# BigDigit.net
KiCad netlist of a schematic drawn in EAGLE
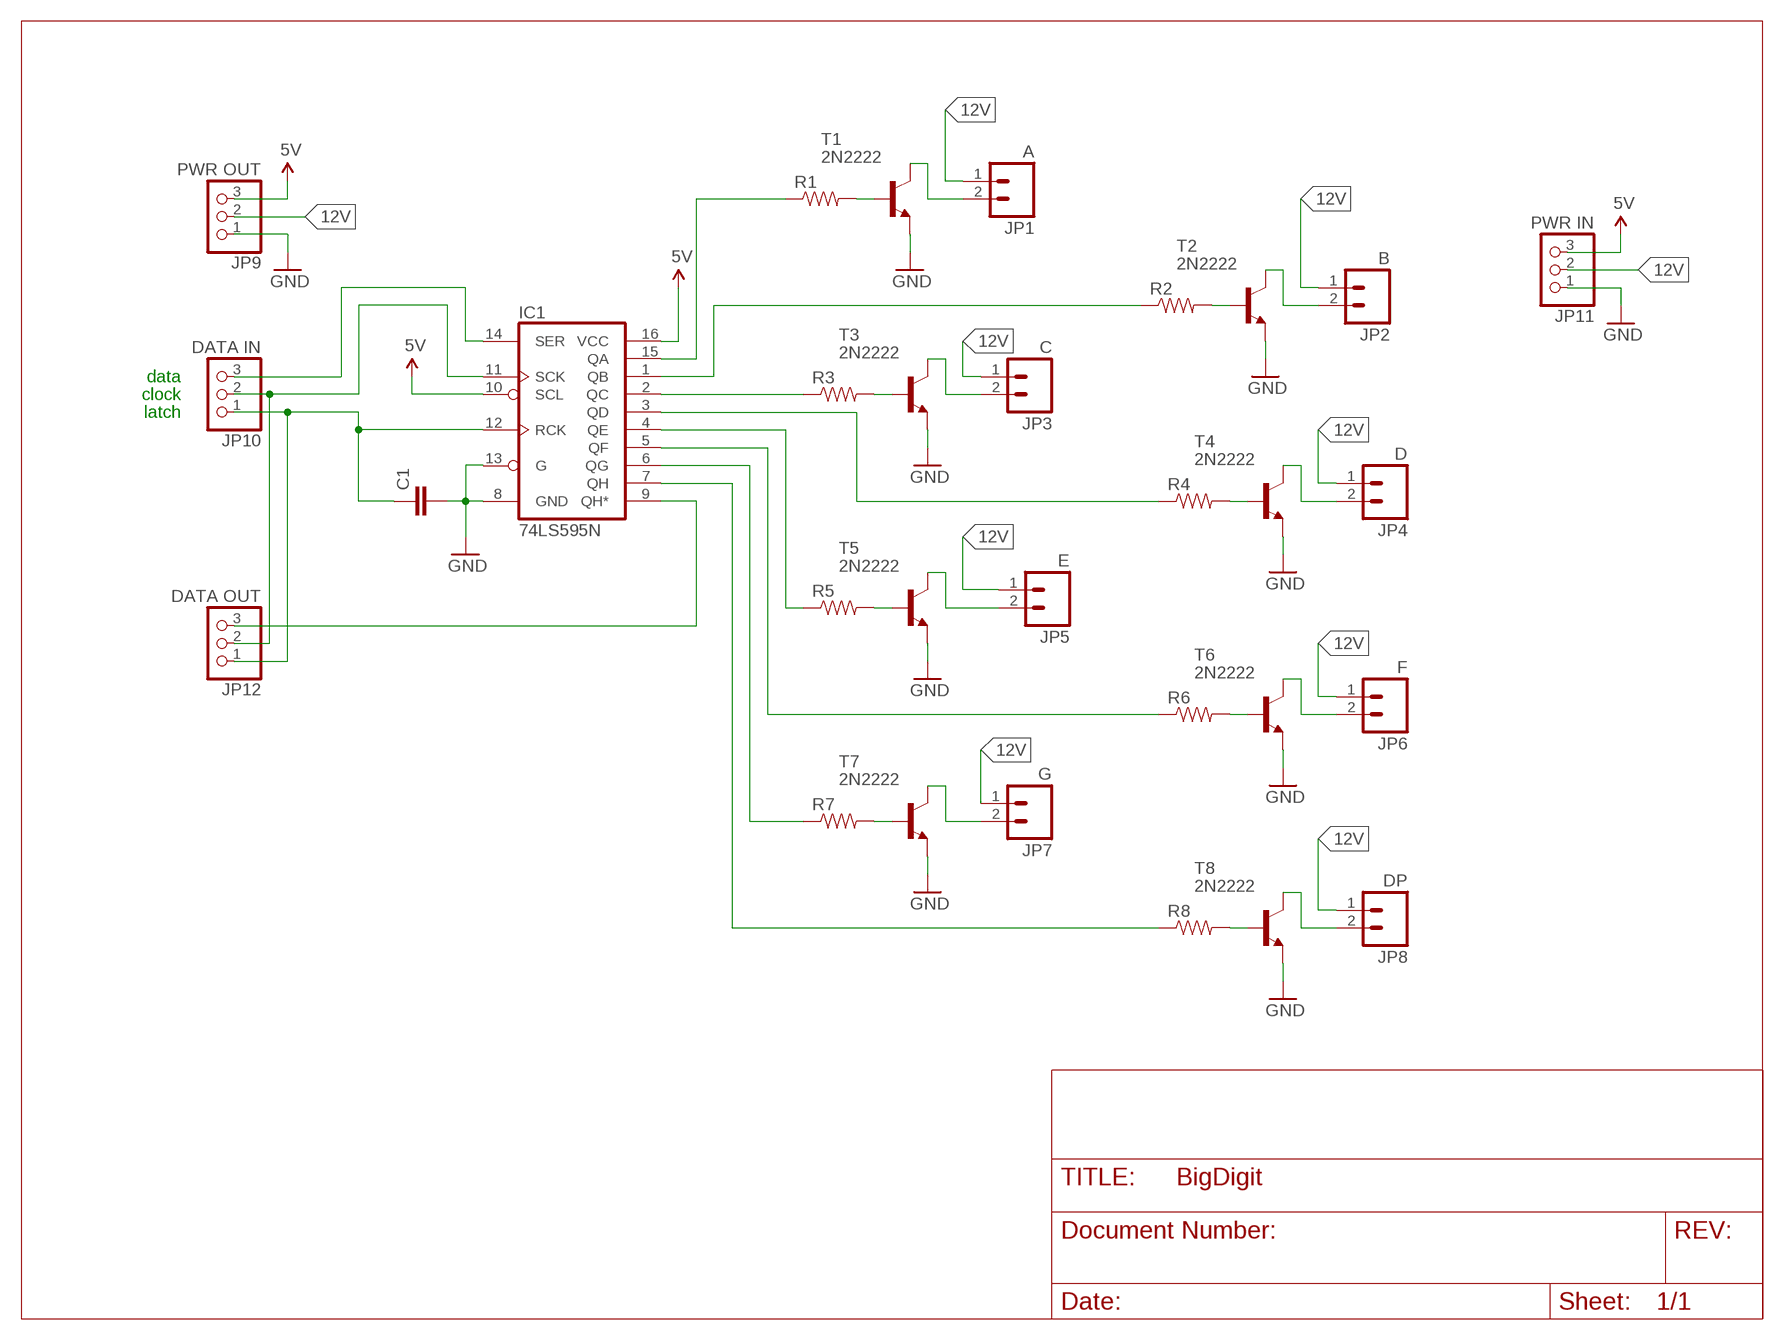
[diagram p0: schematic, sheet 1]

(export (version "E")
  (design (tool "Eeschema 10.0.6"))
  (components
    (comp (ref "C1")
      (value "0.1UF-50V-20%(PTH)KIT-EZ")
      (footprint "eagle-import:CAP-PTH-SMALL-KIT")
      (libsource (lib "eagle-import") (part "0.1UF-50V-20%(PTH)KIT-EZ"))
    )
    (comp (ref "IC1")
      (value "74LS595N")
      (footprint "eagle-import:DIL16")
      (libsource (lib "eagle-import") (part "74595NLS"))
    )
    (comp (ref "JP1")
      (value "A")
      (footprint "eagle-import:1X02")
      (libsource (lib "eagle-import") (part "M02PTH"))
    )
    (comp (ref "JP2")
      (value "B")
      (footprint "eagle-import:1X02")
      (libsource (lib "eagle-import") (part "M02PTH"))
    )
    (comp (ref "JP3")
      (value "C")
      (footprint "eagle-import:1X02")
      (libsource (lib "eagle-import") (part "M02PTH"))
    )
    (comp (ref "JP4")
      (value "D")
      (footprint "eagle-import:1X02")
      (libsource (lib "eagle-import") (part "M02PTH"))
    )
    (comp (ref "JP5")
      (value "E")
      (footprint "eagle-import:1X02")
      (libsource (lib "eagle-import") (part "M02PTH"))
    )
    (comp (ref "JP6")
      (value "F")
      (footprint "eagle-import:1X02")
      (libsource (lib "eagle-import") (part "M02PTH"))
    )
    (comp (ref "JP7")
      (value "G")
      (footprint "eagle-import:1X02")
      (libsource (lib "eagle-import") (part "M02PTH"))
    )
    (comp (ref "JP8")
      (value "DP")
      (footprint "eagle-import:1X02")
      (libsource (lib "eagle-import") (part "M02PTH"))
    )
    (comp (ref "JP9")
      (value "PWR OUT")
      (footprint "eagle-import:1X03-CLEANBIG")
      (libsource (lib "eagle-import") (part "PINHD-1X3CB"))
    )
    (comp (ref "JP10")
      (value "DATA IN")
      (footprint "eagle-import:1X03-CLEANBIG")
      (libsource (lib "eagle-import") (part "PINHD-1X3CB"))
    )
    (comp (ref "JP11")
      (value "PWR IN")
      (footprint "eagle-import:1X03-CLEANBIG")
      (libsource (lib "eagle-import") (part "PINHD-1X3CB"))
    )
    (comp (ref "JP12")
      (value "DATA OUT")
      (footprint "eagle-import:1X03-CLEANBIG")
      (libsource (lib "eagle-import") (part "PINHD-1X3CB"))
    )
    (comp (ref "R1")
      (value "RESISTORPTH-1/4W-VERT")
      (footprint "eagle-import:AXIAL-0.1")
      (libsource (lib "eagle-import") (part "RESISTORPTH-1/4W-VERT"))
    )
    (comp (ref "R2")
      (value "RESISTORPTH-1/4W-VERT")
      (footprint "eagle-import:AXIAL-0.1")
      (libsource (lib "eagle-import") (part "RESISTORPTH-1/4W-VERT"))
    )
    (comp (ref "R3")
      (value "RESISTORPTH-1/4W-VERT")
      (footprint "eagle-import:AXIAL-0.1")
      (libsource (lib "eagle-import") (part "RESISTORPTH-1/4W-VERT"))
    )
    (comp (ref "R4")
      (value "RESISTORPTH-1/4W-VERT")
      (footprint "eagle-import:AXIAL-0.1")
      (libsource (lib "eagle-import") (part "RESISTORPTH-1/4W-VERT"))
    )
    (comp (ref "R5")
      (value "RESISTORPTH-1/4W-VERT")
      (footprint "eagle-import:AXIAL-0.1")
      (libsource (lib "eagle-import") (part "RESISTORPTH-1/4W-VERT"))
    )
    (comp (ref "R6")
      (value "RESISTORPTH-1/4W-VERT")
      (footprint "eagle-import:AXIAL-0.1")
      (libsource (lib "eagle-import") (part "RESISTORPTH-1/4W-VERT"))
    )
    (comp (ref "R7")
      (value "RESISTORPTH-1/4W-VERT")
      (footprint "eagle-import:AXIAL-0.1")
      (libsource (lib "eagle-import") (part "RESISTORPTH-1/4W-VERT"))
    )
    (comp (ref "R8")
      (value "RESISTORPTH-1/4W-VERT")
      (footprint "eagle-import:AXIAL-0.1")
      (libsource (lib "eagle-import") (part "RESISTORPTH-1/4W-VERT"))
    )
    (comp (ref "T1")
      (value "2N2222")
      (footprint "eagle-import:TO92-EBC-OVAL")
      (libsource (lib "eagle-import") (part "2N2222"))
    )
    (comp (ref "T2")
      (value "2N2222")
      (footprint "eagle-import:TO92-EBC-OVAL")
      (libsource (lib "eagle-import") (part "2N2222"))
    )
    (comp (ref "T3")
      (value "2N2222")
      (footprint "eagle-import:TO92-EBC-OVAL")
      (libsource (lib "eagle-import") (part "2N2222"))
    )
    (comp (ref "T4")
      (value "2N2222")
      (footprint "eagle-import:TO92-EBC-OVAL")
      (libsource (lib "eagle-import") (part "2N2222"))
    )
    (comp (ref "T5")
      (value "2N2222")
      (footprint "eagle-import:TO92-EBC-OVAL")
      (libsource (lib "eagle-import") (part "2N2222"))
    )
    (comp (ref "T6")
      (value "2N2222")
      (footprint "eagle-import:TO92-EBC-OVAL")
      (libsource (lib "eagle-import") (part "2N2222"))
    )
    (comp (ref "T7")
      (value "2N2222")
      (footprint "eagle-import:TO92-EBC-OVAL")
      (libsource (lib "eagle-import") (part "2N2222"))
    )
    (comp (ref "T8")
      (value "2N2222")
      (footprint "eagle-import:TO92-EBC-OVAL")
      (libsource (lib "eagle-import") (part "2N2222"))
    )
  )
  (nets
    (net (code "1") (name "5V") (class "Default")
      (node (ref "IC1") (pin "10") (pinfunction "SCL_10") (pintype "input"))
      (node (ref "IC1") (pin "16") (pinfunction "VCC_16") (pintype "power_in"))
      (node (ref "JP11") (pin "3") (pinfunction "3_3") (pintype "passive"))
      (node (ref "JP9") (pin "3") (pinfunction "3_3") (pintype "passive"))
    )
    (net (code "2") (name "12V") (class "Default")
      (node (ref "JP1") (pin "1") (pinfunction "1_1") (pintype "passive"))
      (node (ref "JP11") (pin "2") (pinfunction "2_2") (pintype "passive"))
      (node (ref "JP2") (pin "1") (pinfunction "1_1") (pintype "passive"))
      (node (ref "JP3") (pin "1") (pinfunction "1_1") (pintype "passive"))
      (node (ref "JP4") (pin "1") (pinfunction "1_1") (pintype "passive"))
      (node (ref "JP5") (pin "1") (pinfunction "1_1") (pintype "passive"))
      (node (ref "JP6") (pin "1") (pinfunction "1_1") (pintype "passive"))
      (node (ref "JP7") (pin "1") (pinfunction "1_1") (pintype "passive"))
      (node (ref "JP8") (pin "1") (pinfunction "1_1") (pintype "passive"))
      (node (ref "JP9") (pin "2") (pinfunction "2_2") (pintype "passive"))
    )
    (net (code "3") (name "GND") (class "Default")
      (node (ref "C1") (pin "2") (pinfunction "2_2") (pintype "passive"))
      (node (ref "IC1") (pin "13") (pinfunction "G_13") (pintype "input"))
      (node (ref "IC1") (pin "8") (pinfunction "GND_8") (pintype "power_in"))
      (node (ref "JP11") (pin "1") (pinfunction "1_1") (pintype "passive"))
      (node (ref "JP9") (pin "1") (pinfunction "1_1") (pintype "passive"))
      (node (ref "T1") (pin "E") (pinfunction "E_E") (pintype "passive"))
      (node (ref "T2") (pin "E") (pinfunction "E_E") (pintype "passive"))
      (node (ref "T3") (pin "E") (pinfunction "E_E") (pintype "passive"))
      (node (ref "T4") (pin "E") (pinfunction "E_E") (pintype "passive"))
      (node (ref "T5") (pin "E") (pinfunction "E_E") (pintype "passive"))
      (node (ref "T6") (pin "E") (pinfunction "E_E") (pintype "passive"))
      (node (ref "T7") (pin "E") (pinfunction "E_E") (pintype "passive"))
      (node (ref "T8") (pin "E") (pinfunction "E_E") (pintype "passive"))
    )
    (net (code "4") (name "Net-(IC1-QA)") (class "Default")
      (node (ref "IC1") (pin "15") (pinfunction "QA_15") (pintype "tri_state"))
      (node (ref "R1") (pin "P$1") (pinfunction "1_P$1") (pintype "passive"))
    )
    (net (code "5") (name "Net-(IC1-QB)") (class "Default")
      (node (ref "IC1") (pin "1") (pinfunction "QB_1") (pintype "tri_state"))
      (node (ref "R2") (pin "P$1") (pinfunction "1_P$1") (pintype "passive"))
    )
    (net (code "6") (name "Net-(IC1-QC)") (class "Default")
      (node (ref "IC1") (pin "2") (pinfunction "QC_2") (pintype "tri_state"))
      (node (ref "R3") (pin "P$1") (pinfunction "1_P$1") (pintype "passive"))
    )
    (net (code "7") (name "Net-(IC1-QD)") (class "Default")
      (node (ref "IC1") (pin "3") (pinfunction "QD_3") (pintype "tri_state"))
      (node (ref "R4") (pin "P$1") (pinfunction "1_P$1") (pintype "passive"))
    )
    (net (code "8") (name "Net-(IC1-QE)") (class "Default")
      (node (ref "IC1") (pin "4") (pinfunction "QE_4") (pintype "tri_state"))
      (node (ref "R5") (pin "P$1") (pinfunction "1_P$1") (pintype "passive"))
    )
    (net (code "9") (name "Net-(IC1-QF)") (class "Default")
      (node (ref "IC1") (pin "5") (pinfunction "QF_5") (pintype "tri_state"))
      (node (ref "R6") (pin "P$1") (pinfunction "1_P$1") (pintype "passive"))
    )
    (net (code "10") (name "Net-(IC1-QG)") (class "Default")
      (node (ref "IC1") (pin "6") (pinfunction "QG_6") (pintype "tri_state"))
      (node (ref "R7") (pin "P$1") (pinfunction "1_P$1") (pintype "passive"))
    )
    (net (code "11") (name "Net-(IC1-QH)") (class "Default")
      (node (ref "IC1") (pin "7") (pinfunction "QH_7") (pintype "tri_state"))
      (node (ref "R8") (pin "P$1") (pinfunction "1_P$1") (pintype "passive"))
    )
    (net (code "12") (name "Net-(IC1-QH*)") (class "Default")
      (node (ref "IC1") (pin "9") (pinfunction "QH*_9") (pintype "tri_state"))
      (node (ref "JP12") (pin "3") (pinfunction "3_3") (pintype "passive"))
    )
    (net (code "13") (name "Net-(IC1-RCK)") (class "Default")
      (node (ref "C1") (pin "1") (pinfunction "1_1") (pintype "passive"))
      (node (ref "IC1") (pin "12") (pinfunction "RCK_12") (pintype "input"))
      (node (ref "JP10") (pin "1") (pinfunction "1_1") (pintype "passive"))
      (node (ref "JP12") (pin "1") (pinfunction "1_1") (pintype "passive"))
    )
    (net (code "14") (name "Net-(IC1-SCK)") (class "Default")
      (node (ref "IC1") (pin "11") (pinfunction "SCK_11") (pintype "input"))
      (node (ref "JP10") (pin "2") (pinfunction "2_2") (pintype "passive"))
      (node (ref "JP12") (pin "2") (pinfunction "2_2") (pintype "passive"))
    )
    (net (code "15") (name "Net-(IC1-SER)") (class "Default")
      (node (ref "IC1") (pin "14") (pinfunction "SER_14") (pintype "input"))
      (node (ref "JP10") (pin "3") (pinfunction "3_3") (pintype "passive"))
    )
    (net (code "16") (name "Net-(JP1-Pad2)") (class "Default")
      (node (ref "JP1") (pin "2") (pinfunction "2_2") (pintype "passive"))
      (node (ref "T1") (pin "C") (pinfunction "C_C") (pintype "passive"))
    )
    (net (code "17") (name "Net-(JP2-Pad2)") (class "Default")
      (node (ref "JP2") (pin "2") (pinfunction "2_2") (pintype "passive"))
      (node (ref "T2") (pin "C") (pinfunction "C_C") (pintype "passive"))
    )
    (net (code "18") (name "Net-(JP3-Pad2)") (class "Default")
      (node (ref "JP3") (pin "2") (pinfunction "2_2") (pintype "passive"))
      (node (ref "T3") (pin "C") (pinfunction "C_C") (pintype "passive"))
    )
    (net (code "19") (name "Net-(JP4-Pad2)") (class "Default")
      (node (ref "JP4") (pin "2") (pinfunction "2_2") (pintype "passive"))
      (node (ref "T4") (pin "C") (pinfunction "C_C") (pintype "passive"))
    )
    (net (code "20") (name "Net-(JP5-Pad2)") (class "Default")
      (node (ref "JP5") (pin "2") (pinfunction "2_2") (pintype "passive"))
      (node (ref "T5") (pin "C") (pinfunction "C_C") (pintype "passive"))
    )
    (net (code "21") (name "Net-(JP6-Pad2)") (class "Default")
      (node (ref "JP6") (pin "2") (pinfunction "2_2") (pintype "passive"))
      (node (ref "T6") (pin "C") (pinfunction "C_C") (pintype "passive"))
    )
    (net (code "22") (name "Net-(JP7-Pad2)") (class "Default")
      (node (ref "JP7") (pin "2") (pinfunction "2_2") (pintype "passive"))
      (node (ref "T7") (pin "C") (pinfunction "C_C") (pintype "passive"))
    )
    (net (code "23") (name "Net-(JP8-Pad2)") (class "Default")
      (node (ref "JP8") (pin "2") (pinfunction "2_2") (pintype "passive"))
      (node (ref "T8") (pin "C") (pinfunction "C_C") (pintype "passive"))
    )
    (net (code "24") (name "Net-(R1-2)") (class "Default")
      (node (ref "R1") (pin "P$2") (pinfunction "2_P$2") (pintype "passive"))
      (node (ref "T1") (pin "B") (pinfunction "B_B") (pintype "passive"))
    )
    (net (code "25") (name "Net-(R2-2)") (class "Default")
      (node (ref "R2") (pin "P$2") (pinfunction "2_P$2") (pintype "passive"))
      (node (ref "T2") (pin "B") (pinfunction "B_B") (pintype "passive"))
    )
    (net (code "26") (name "Net-(R3-2)") (class "Default")
      (node (ref "R3") (pin "P$2") (pinfunction "2_P$2") (pintype "passive"))
      (node (ref "T3") (pin "B") (pinfunction "B_B") (pintype "passive"))
    )
    (net (code "27") (name "Net-(R4-2)") (class "Default")
      (node (ref "R4") (pin "P$2") (pinfunction "2_P$2") (pintype "passive"))
      (node (ref "T4") (pin "B") (pinfunction "B_B") (pintype "passive"))
    )
    (net (code "28") (name "Net-(R5-2)") (class "Default")
      (node (ref "R5") (pin "P$2") (pinfunction "2_P$2") (pintype "passive"))
      (node (ref "T5") (pin "B") (pinfunction "B_B") (pintype "passive"))
    )
    (net (code "29") (name "Net-(R6-2)") (class "Default")
      (node (ref "R6") (pin "P$2") (pinfunction "2_P$2") (pintype "passive"))
      (node (ref "T6") (pin "B") (pinfunction "B_B") (pintype "passive"))
    )
    (net (code "30") (name "Net-(R7-2)") (class "Default")
      (node (ref "R7") (pin "P$2") (pinfunction "2_P$2") (pintype "passive"))
      (node (ref "T7") (pin "B") (pinfunction "B_B") (pintype "passive"))
    )
    (net (code "31") (name "Net-(R8-2)") (class "Default")
      (node (ref "R8") (pin "P$2") (pinfunction "2_P$2") (pintype "passive"))
      (node (ref "T8") (pin "B") (pinfunction "B_B") (pintype "passive"))
    )
  )
)
